# miTest.net
KiCad netlist of a schematic drawn in Altium Designer
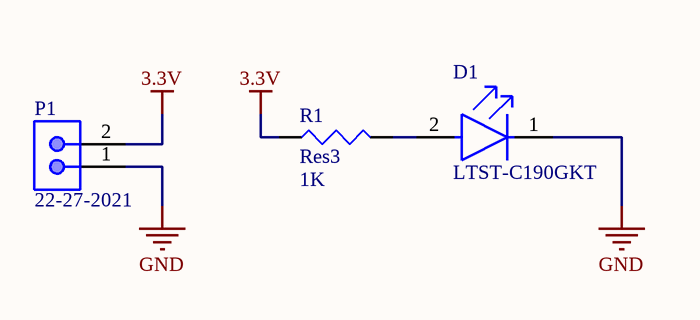
[diagram p0: miTest.SchDoc]

(export (version "E")
  (design (tool "Eeschema 10.0.6"))
  (components
    (comp (ref "D1")
      (value "LTST-C190GKT")
      (footprint "FP-LTST-C190GKT-MFG")
      (description "LED GREEN CLEAR CHIP SMD")
      (fields (field (name "VOLTAGE") "2V"))
      (libsource (lib "Altium Content Vault") (part "8706943c75ba83719d021d2fdc84c58"))
    )
    (comp (ref "P1")
      (value "22-27-2021")
      (footprint "MOLX-22-27-2021_V")
      (fields (field (name "MANUFACTURER") "Molex") (field (name "PARTNUMBER") "0022272021"))
      (libsource (lib "Altium Content Vault") (part "CN-1P-M-R2"))
    )
    (comp (ref "R1")
      (value "Res3")
      (footprint "J1-0603")
      (description "Resistor")
      (fields (field (name "ALTIUM_VALUE") "1K") (field (name "PUBLISHER") "Altium Limited"))
      (libsource (lib "Miscellaneous Devices") (part "Res3"))
    )
  )
  (nets
    (net (code "1") (name "3.3V") (class "Default")
      (node (ref "P1") (pin "2") (pinfunction "2_2") (pintype "passive"))
      (node (ref "R1") (pin "1") (pinfunction "1_1") (pintype "passive"))
    )
    (net (code "2") (name "GND") (class "Default")
      (node (ref "D1") (pin "1") (pinfunction "C_1") (pintype "passive"))
      (node (ref "P1") (pin "1") (pinfunction "1_1") (pintype "passive"))
    )
    (net (code "3") (name "Net-(D1-A)") (class "Default")
      (node (ref "D1") (pin "2") (pinfunction "A_2") (pintype "passive"))
      (node (ref "R1") (pin "2") (pinfunction "2_2") (pintype "passive"))
    )
  )
)
